# PLL.net
KiCad netlist of a schematic drawn in Altium Designer
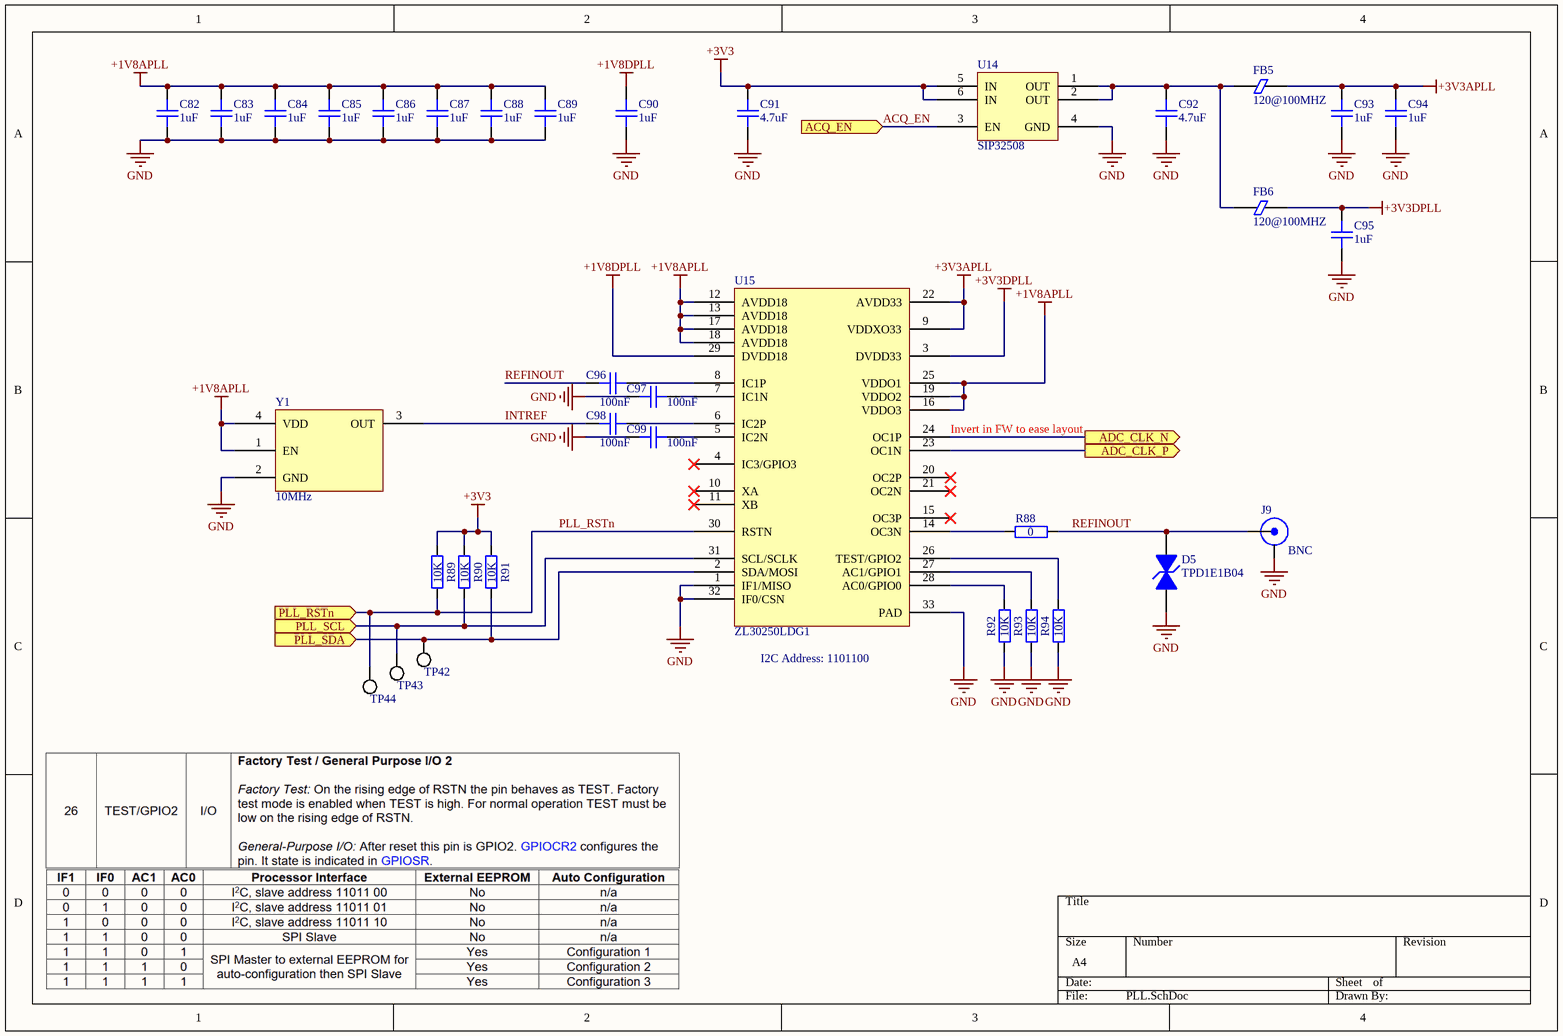
[diagram p0: PLL.SchDoc]

(export (version "E")
  (design (tool "Eeschema 10.0.6"))
  (components
    (comp (ref "C82")
      (value "1uF")
      (footprint "GEN_C_0402")
      (libsource (lib "DSO") (part "CAP 1uF 25V X5R 0402"))
    )
    (comp (ref "C83")
      (value "1uF")
      (footprint "GEN_C_0402")
      (libsource (lib "DSO") (part "CAP 1uF 25V X5R 0402"))
    )
    (comp (ref "C84")
      (value "1uF")
      (footprint "GEN_C_0402")
      (libsource (lib "DSO") (part "CAP 1uF 25V X5R 0402"))
    )
    (comp (ref "C85")
      (value "1uF")
      (footprint "GEN_C_0402")
      (libsource (lib "DSO") (part "CAP 1uF 25V X5R 0402"))
    )
    (comp (ref "C86")
      (value "1uF")
      (footprint "GEN_C_0402")
      (libsource (lib "DSO") (part "CAP 1uF 25V X5R 0402"))
    )
    (comp (ref "C87")
      (value "1uF")
      (footprint "GEN_C_0402")
      (libsource (lib "DSO") (part "CAP 1uF 25V X5R 0402"))
    )
    (comp (ref "C88")
      (value "1uF")
      (footprint "GEN_C_0402")
      (libsource (lib "DSO") (part "CAP 1uF 25V X5R 0402"))
    )
    (comp (ref "C89")
      (value "1uF")
      (footprint "GEN_C_0402")
      (libsource (lib "DSO") (part "CAP 1uF 25V X5R 0402"))
    )
    (comp (ref "C90")
      (value "1uF")
      (footprint "GEN_C_0402")
      (libsource (lib "DSO") (part "CAP 1uF 25V X5R 0402"))
    )
    (comp (ref "C91")
      (value "4.7uF")
      (footprint "GEN_C_0402")
      (libsource (lib "DSO") (part "CAP 4.7uF 6.3V X5R 0402"))
    )
    (comp (ref "C92")
      (value "4.7uF")
      (footprint "GEN_C_0402")
      (libsource (lib "DSO") (part "CAP 4.7uF 6.3V X5R 0402"))
    )
    (comp (ref "C93")
      (value "1uF")
      (footprint "GEN_C_0402")
      (libsource (lib "DSO") (part "CAP 1uF 25V X5R 0402"))
    )
    (comp (ref "C94")
      (value "1uF")
      (footprint "GEN_C_0402")
      (libsource (lib "DSO") (part "CAP 1uF 25V X5R 0402"))
    )
    (comp (ref "C95")
      (value "1uF")
      (footprint "GEN_C_0402")
      (libsource (lib "DSO") (part "CAP 1uF 25V X5R 0402"))
    )
    (comp (ref "C96")
      (value "100nF")
      (footprint "GEN_C_0402")
      (libsource (lib "DSO") (part "CAP 100nF 16V X7R 0402"))
    )
    (comp (ref "C97")
      (value "100nF")
      (footprint "GEN_C_0402")
      (libsource (lib "DSO") (part "CAP 100nF 16V X7R 0402"))
    )
    (comp (ref "C98")
      (value "100nF")
      (footprint "GEN_C_0402")
      (libsource (lib "DSO") (part "CAP 100nF 16V X7R 0402"))
    )
    (comp (ref "C99")
      (value "100nF")
      (footprint "GEN_C_0402")
      (libsource (lib "DSO") (part "CAP 100nF 16V X7R 0402"))
    )
    (comp (ref "D5")
      (value "TPD1E1B04")
      (footprint "TI_X1SON_DPY0002A")
      (libsource (lib "DSO") (part "TVS TPD1E1B04"))
    )
    (comp (ref "FB5")
      (value "120@100MHZ")
      (footprint "GEN_R_0402")
      (libsource (lib "DSO") (part "FERRITE BEAD 120 OHM 0402"))
    )
    (comp (ref "FB6")
      (value "120@100MHZ")
      (footprint "GEN_R_0402")
      (libsource (lib "DSO") (part "FERRITE BEAD 120 OHM 0402"))
    )
    (comp (ref "J9") (value "BNC") (footprint "MOL_0731000105") (libsource (lib "DSO") (part "BNC JACK R/A")))
    (comp (ref "R88")
      (value "0")
      (footprint "GEN_R_0402")
      (libsource (lib "DSO") (part "RES 0 OHM 1/16W 0402"))
    )
    (comp (ref "R89")
      (value "10K")
      (footprint "GEN_R_0402")
      (fields (field (name "TOLERANCE") "1%"))
      (libsource (lib "") (part "RES 10K OHM 1% 1/10W 0402_1"))
    )
    (comp (ref "R90")
      (value "10K")
      (footprint "GEN_R_0402")
      (fields (field (name "TOLERANCE") "1%"))
      (libsource (lib "") (part "RES 10K OHM 1% 1/10W 0402_1"))
    )
    (comp (ref "R91")
      (value "10K")
      (footprint "GEN_R_0402")
      (fields (field (name "TOLERANCE") "1%"))
      (libsource (lib "") (part "RES 10K OHM 1% 1/10W 0402_1"))
    )
    (comp (ref "R92")
      (value "10K")
      (footprint "GEN_R_0402")
      (fields (field (name "TOLERANCE") "1%"))
      (libsource (lib "DSO") (part "RES 10K OHM 1% 1/10W 0402"))
    )
    (comp (ref "R93")
      (value "10K")
      (footprint "GEN_R_0402")
      (fields (field (name "TOLERANCE") "1%"))
      (libsource (lib "DSO") (part "RES 10K OHM 1% 1/10W 0402"))
    )
    (comp (ref "R94")
      (value "10K")
      (footprint "GEN_R_0402")
      (fields (field (name "TOLERANCE") "1%"))
      (libsource (lib "DSO") (part "RES 10K OHM 1% 1/10W 0402"))
    )
    (comp (ref "TP42") (value "PCB") (footprint "GEN_TP_PCB") (libsource (lib "DSO") (part "TP PCB 1mm")))
    (comp (ref "TP43") (value "PCB") (footprint "GEN_TP_PCB") (libsource (lib "DSO") (part "TP PCB 1mm")))
    (comp (ref "TP44") (value "PCB") (footprint "GEN_TP_PCB") (libsource (lib "DSO") (part "TP PCB 1mm")))
    (comp (ref "U14")
      (value "SIP32508")
      (footprint "VISH_TSOT6")
      (libsource (lib "DSO") (part "IC SWITCH LOAD SIP32508"))
    )
    (comp (ref "U15")
      (value "ZL30250LDG1")
      (footprint "MC_QFN32_ZL30250")
      (libsource (lib "DSO") (part "IC CLK GEN ZL30250LDG1"))
    )
    (comp (ref "Y1")
      (value "10MHz")
      (footprint "ECS_TXO-3225")
      (libsource (lib "DSO") (part "OSC 10MHz ECS-TXO-3225MV"))
    )
  )
  (nets
    (net (code "1") (name "+1V8APLL") (class "Default")
      (node (ref "C82") (pin "1") (pinfunction "1_1") (pintype "passive"))
      (node (ref "C83") (pin "1") (pinfunction "1_1") (pintype "passive"))
      (node (ref "C84") (pin "1") (pinfunction "1_1") (pintype "passive"))
      (node (ref "C85") (pin "1") (pinfunction "1_1") (pintype "passive"))
      (node (ref "C86") (pin "1") (pinfunction "1_1") (pintype "passive"))
      (node (ref "C87") (pin "1") (pinfunction "1_1") (pintype "passive"))
      (node (ref "C88") (pin "1") (pinfunction "1_1") (pintype "passive"))
      (node (ref "C89") (pin "1") (pinfunction "1_1") (pintype "passive"))
      (node (ref "U15") (pin "12") (pinfunction "AVDD18_12") (pintype "passive"))
      (node (ref "U15") (pin "13") (pinfunction "AVDD18_13") (pintype "passive"))
      (node (ref "U15") (pin "16") (pinfunction "VDDO3_16") (pintype "passive"))
      (node (ref "U15") (pin "17") (pinfunction "AVDD18_17") (pintype "passive"))
      (node (ref "U15") (pin "18") (pinfunction "AVDD18_18") (pintype "passive"))
      (node (ref "U15") (pin "19") (pinfunction "VDDO2_19") (pintype "passive"))
      (node (ref "U15") (pin "25") (pinfunction "VDDO1_25") (pintype "passive"))
      (node (ref "Y1") (pin "1") (pinfunction "EN_1") (pintype "passive"))
      (node (ref "Y1") (pin "4") (pinfunction "VDD_4") (pintype "power_in"))
    )
    (net (code "2") (name "+1V8DPLL") (class "Default")
      (node (ref "C90") (pin "1") (pinfunction "1_1") (pintype "passive"))
      (node (ref "U15") (pin "29") (pinfunction "DVDD18_29") (pintype "passive"))
    )
    (net (code "3") (name "+3V3") (class "Default")
      (node (ref "C91") (pin "2") (pinfunction "2_2") (pintype "passive"))
      (node (ref "R89") (pin "2") (pinfunction "2_2") (pintype "passive"))
      (node (ref "R90") (pin "2") (pinfunction "2_2") (pintype "passive"))
      (node (ref "R91") (pin "2") (pinfunction "2_2") (pintype "passive"))
      (node (ref "U14") (pin "5") (pinfunction "IN_5") (pintype "passive"))
      (node (ref "U14") (pin "6") (pinfunction "IN_6") (pintype "passive"))
    )
    (net (code "4") (name "+3V3APLL") (class "Default")
      (node (ref "C93") (pin "1") (pinfunction "1_1") (pintype "passive"))
      (node (ref "C94") (pin "1") (pinfunction "1_1") (pintype "passive"))
      (node (ref "FB5") (pin "2") (pinfunction "2_2") (pintype "passive"))
      (node (ref "U15") (pin "22") (pinfunction "AVDD33_22") (pintype "passive"))
      (node (ref "U15") (pin "9") (pinfunction "VDDXO33_9") (pintype "passive"))
    )
    (net (code "5") (name "+3V3DPLL") (class "Default")
      (node (ref "C95") (pin "1") (pinfunction "1_1") (pintype "passive"))
      (node (ref "FB6") (pin "2") (pinfunction "2_2") (pintype "passive"))
      (node (ref "U15") (pin "3") (pinfunction "DVDD33_3") (pintype "passive"))
    )
    (net (code "6") (name "/ACQ_EN") (class "Default")
      (node (ref "U14") (pin "3") (pinfunction "EN_3") (pintype "passive"))
    )
    (net (code "7") (name "/ADC_CLK_N") (class "Default")
      (node (ref "U15") (pin "24") (pinfunction "OC1P_24") (pintype "passive"))
    )
    (net (code "8") (name "/ADC_CLK_P") (class "Default")
      (node (ref "U15") (pin "23") (pinfunction "OC1N_23") (pintype "passive"))
    )
    (net (code "9") (name "/INTREF") (class "Default")
      (node (ref "C98") (pin "2") (pinfunction "2_2") (pintype "passive"))
      (node (ref "Y1") (pin "3") (pinfunction "OUT_3") (pintype "passive"))
    )
    (net (code "10") (name "/PLL_RSTn") (class "Default")
      (node (ref "R89") (pin "1") (pinfunction "1_1") (pintype "passive"))
      (node (ref "TP44") (pin "1") (pinfunction "1_1") (pintype "passive"))
      (node (ref "U15") (pin "30") (pinfunction "RSTN_30") (pintype "passive"))
    )
    (net (code "11") (name "/PLL_SCL") (class "Default")
      (node (ref "R90") (pin "1") (pinfunction "1_1") (pintype "passive"))
      (node (ref "TP43") (pin "1") (pinfunction "1_1") (pintype "passive"))
      (node (ref "U15") (pin "31") (pinfunction "SCL/SCLK_31") (pintype "passive"))
    )
    (net (code "12") (name "/PLL_SDA") (class "Default")
      (node (ref "R91") (pin "1") (pinfunction "1_1") (pintype "passive"))
      (node (ref "TP42") (pin "1") (pinfunction "1_1") (pintype "passive"))
      (node (ref "U15") (pin "2") (pinfunction "SDA/MOSI_2") (pintype "passive"))
    )
    (net (code "13") (name "/REFINOUT") (class "Default")
      (node (ref "C96") (pin "2") (pinfunction "2_2") (pintype "passive"))
      (node (ref "D5") (pin "1") (pinfunction "K_1") (pintype "passive"))
      (node (ref "J9") (pin "1") (pinfunction "Signal_1") (pintype "passive"))
      (node (ref "R88") (pin "2") (pinfunction "2_2") (pintype "passive"))
    )
    (net (code "14") (name "GND") (class "Default")
      (node (ref "C82") (pin "2") (pinfunction "2_2") (pintype "passive"))
      (node (ref "C83") (pin "2") (pinfunction "2_2") (pintype "passive"))
      (node (ref "C84") (pin "2") (pinfunction "2_2") (pintype "passive"))
      (node (ref "C85") (pin "2") (pinfunction "2_2") (pintype "passive"))
      (node (ref "C86") (pin "2") (pinfunction "2_2") (pintype "passive"))
      (node (ref "C87") (pin "2") (pinfunction "2_2") (pintype "passive"))
      (node (ref "C88") (pin "2") (pinfunction "2_2") (pintype "passive"))
      (node (ref "C89") (pin "2") (pinfunction "2_2") (pintype "passive"))
      (node (ref "C90") (pin "2") (pinfunction "2_2") (pintype "passive"))
      (node (ref "C91") (pin "1") (pinfunction "1_1") (pintype "passive"))
      (node (ref "C92") (pin "1") (pinfunction "1_1") (pintype "passive"))
      (node (ref "C93") (pin "2") (pinfunction "2_2") (pintype "passive"))
      (node (ref "C94") (pin "2") (pinfunction "2_2") (pintype "passive"))
      (node (ref "C95") (pin "2") (pinfunction "2_2") (pintype "passive"))
      (node (ref "C97") (pin "2") (pinfunction "2_2") (pintype "passive"))
      (node (ref "C99") (pin "2") (pinfunction "2_2") (pintype "passive"))
      (node (ref "D5") (pin "2") (pinfunction "A_2") (pintype "passive"))
      (node (ref "J9") (pin "2") (pinfunction "SHIELD_2") (pintype "passive"))
      (node (ref "R92") (pin "1") (pinfunction "1_1") (pintype "passive"))
      (node (ref "R93") (pin "1") (pinfunction "1_1") (pintype "passive"))
      (node (ref "R94") (pin "1") (pinfunction "1_1") (pintype "passive"))
      (node (ref "U14") (pin "4") (pinfunction "GND_4") (pintype "passive"))
      (node (ref "U15") (pin "1") (pinfunction "IF1/MISO_1") (pintype "passive"))
      (node (ref "U15") (pin "32") (pinfunction "IF0/CSN_32") (pintype "passive"))
      (node (ref "U15") (pin "33") (pinfunction "PAD_33") (pintype "passive"))
      (node (ref "Y1") (pin "2") (pinfunction "GND_2") (pintype "power_in"))
    )
    (net (code "15") (name "Net-(C92-Pad2)") (class "Default")
      (node (ref "C92") (pin "2") (pinfunction "2_2") (pintype "passive"))
      (node (ref "FB5") (pin "1") (pinfunction "1_1") (pintype "passive"))
      (node (ref "FB6") (pin "1") (pinfunction "1_1") (pintype "passive"))
      (node (ref "U14") (pin "1") (pinfunction "OUT_1") (pintype "passive"))
      (node (ref "U14") (pin "2") (pinfunction "OUT_2") (pintype "passive"))
    )
    (net (code "16") (name "Net-(U15-AC0{slash}GPIO0)") (class "Default")
      (node (ref "R92") (pin "2") (pinfunction "2_2") (pintype "passive"))
      (node (ref "U15") (pin "28") (pinfunction "AC0/GPIO0_28") (pintype "passive"))
    )
    (net (code "17") (name "Net-(U15-AC1{slash}GPIO1)") (class "Default")
      (node (ref "R93") (pin "2") (pinfunction "2_2") (pintype "passive"))
      (node (ref "U15") (pin "27") (pinfunction "AC1/GPIO1_27") (pintype "passive"))
    )
    (net (code "18") (name "Net-(U15-IC1N)") (class "Default")
      (node (ref "C97") (pin "1") (pinfunction "1_1") (pintype "passive"))
      (node (ref "U15") (pin "7") (pinfunction "IC1N_7") (pintype "passive"))
    )
    (net (code "19") (name "Net-(U15-IC1P)") (class "Default")
      (node (ref "C96") (pin "1") (pinfunction "1_1") (pintype "passive"))
      (node (ref "U15") (pin "8") (pinfunction "IC1P_8") (pintype "passive"))
    )
    (net (code "20") (name "Net-(U15-IC2N)") (class "Default")
      (node (ref "C99") (pin "1") (pinfunction "1_1") (pintype "passive"))
      (node (ref "U15") (pin "5") (pinfunction "IC2N_5") (pintype "passive"))
    )
    (net (code "21") (name "Net-(U15-IC2P)") (class "Default")
      (node (ref "C98") (pin "1") (pinfunction "1_1") (pintype "passive"))
      (node (ref "U15") (pin "6") (pinfunction "IC2P_6") (pintype "passive"))
    )
    (net (code "22") (name "Net-(U15-OC3N)") (class "Default")
      (node (ref "R88") (pin "1") (pinfunction "1_1") (pintype "passive"))
      (node (ref "U15") (pin "14") (pinfunction "OC3N_14") (pintype "passive"))
    )
    (net (code "23") (name "Net-(U15-TEST{slash}GPIO2)") (class "Default")
      (node (ref "R94") (pin "2") (pinfunction "2_2") (pintype "passive"))
      (node (ref "U15") (pin "26") (pinfunction "TEST/GPIO2_26") (pintype "passive"))
    )
    (net (code "24") (name "unconnected-(U15-IC3{slash}GPIO3-Pad4)") (class "Default")
      (node (ref "U15") (pin "4") (pinfunction "IC3/GPIO3_4") (pintype "passive+no_connect"))
    )
    (net (code "25") (name "unconnected-(U15-OC2N-Pad21)") (class "Default")
      (node (ref "U15") (pin "21") (pinfunction "OC2N_21") (pintype "passive+no_connect"))
    )
    (net (code "26") (name "unconnected-(U15-OC2P-Pad20)") (class "Default")
      (node (ref "U15") (pin "20") (pinfunction "OC2P_20") (pintype "passive+no_connect"))
    )
    (net (code "27") (name "unconnected-(U15-OC3P-Pad15)") (class "Default")
      (node (ref "U15") (pin "15") (pinfunction "OC3P_15") (pintype "passive+no_connect"))
    )
    (net (code "28") (name "unconnected-(U15-XA-Pad10)") (class "Default")
      (node (ref "U15") (pin "10") (pinfunction "XA_10") (pintype "passive+no_connect"))
    )
    (net (code "29") (name "unconnected-(U15-XB-Pad11)") (class "Default")
      (node (ref "U15") (pin "11") (pinfunction "XB_11") (pintype "passive+no_connect"))
    )
  )
)
